# course.net
KiCad netlist of a schematic drawn in Altium Designer
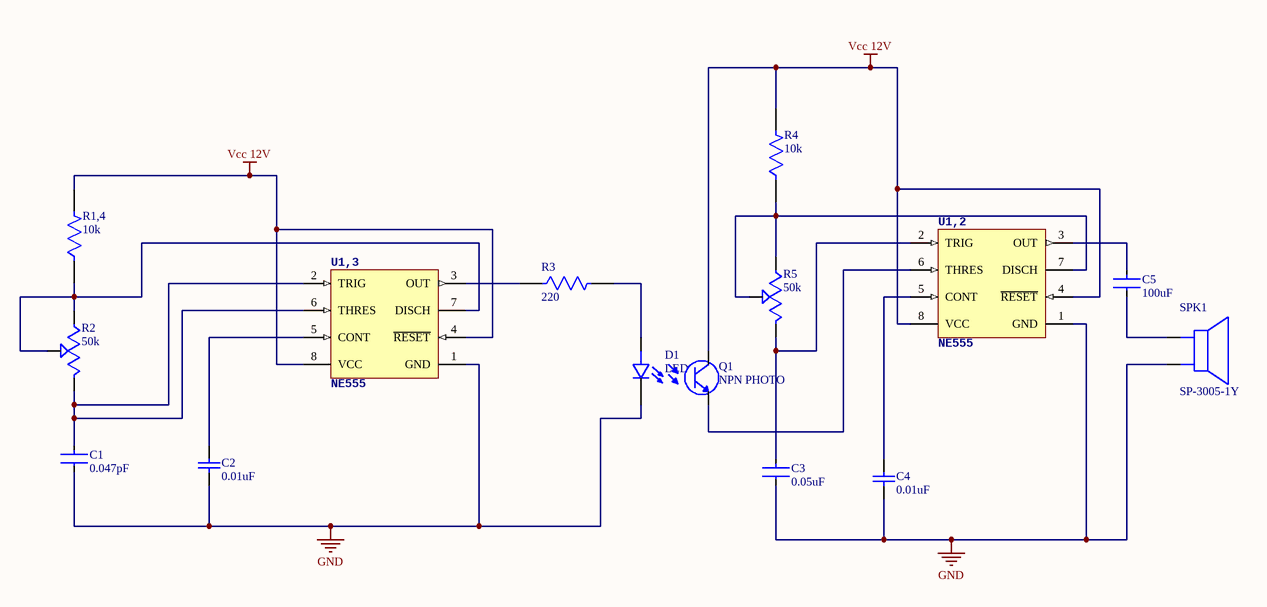
[diagram p0: course.SchDoc]

(export (version "E")
  (design (tool "Eeschema 10.0.6"))
  (components
    (comp (ref "C1")
      (value "0.047pF")
      (footprint "C0603C473M5RAC7867")
      (description "CAP CER 0.047UF 50V X7R 0603")
      (fields (field (name "TOLERANCE") "0.2") (field (name "MANUFACTURER") "KEMET"))
      (libsource (lib "course") (part "C0603C473M5RAC7867"))
    )
    (comp (ref "C2")
      (value "0.01uF")
      (footprint "CAPC1206(3216)100_L")
      (description "Cap Ceramic 0.01uF 50V X7R 10% SMD 1206 125°C Plastic T/R")
      (fields (field (name "TOLERANCE") "Â±10%"))
      (libsource (lib "course") (part "C1206C103K5RAC7025"))
    )
    (comp (ref "C3")
      (value "0.05uF")
      (footprint "FP-C0805C-DN-IPC_A")
      (description "CAP CER 0.056UF 50V 10% X7R 0805")
      (fields
        (field (name "OCTOPART") "https://octopart.com/c0805c563k5ractu-kemet-10470779")
        (field (name "TOLERANCE") "0.1")
      )
      (libsource (lib "course") (part "C0805C563K5RACTU"))
    )
    (comp (ref "C4")
      (value "0.01uF")
      (footprint "CAPC1206(3216)100_L")
      (description "Cap Ceramic 0.01uF 50V X7R 10% SMD 1206 125°C Plastic T/R")
      (fields (field (name "TOLERANCE") "Â±10%"))
      (libsource (lib "course") (part "C1206C103K5RAC7025"))
    )
    (comp (ref "C5")
      (value "100uF")
      (footprint "FP-EMK325A-M-IPC_A")
      (description "CAP CER 100UF 16V X5R 1210")
      (fields
        (field (name "OCTOPART") "https://octopart.com/emk325abj107mm-t-taiyo+yuden-20815747")
        (field (name "MANUFACTURER PART NUMBER") "EMK325ABJ107MM-T")
      )
      (libsource (lib "course") (part "EMK325ABJ107MM-T"))
    )
    (comp (ref "D1")
      (value "LED")
      (description "850 nm 100 mA Â±28Â° Surface Mount High Speed Infrared Emitting Diode")
      (fields (field (name "MP") "VSMY2853G"))
      (libsource (lib "course") (part "VSMY2853G"))
    )
    (comp (ref "Q1")
      (value "NPN PHOTO")
      (footprint "XDCR_VEMT2523X01")
      (description "PHOTOTRANSISTOR 470 TO 1090 NM")
      (fields (field (name "MP") "VEMT2523X01"))
      (libsource (lib "course") (part "VEMT2523X01"))
    )
    (comp (ref "R1,4")
      (value "10k")
      (description "10kΩ ±5% 0.125W 0805 Thick Film Chip Resistor AEC-Q200 compliant")
      (fields (field (name "TOLERANCE") "5%"))
      (libsource (lib "course") (part "RMCF0805JT10K0"))
    )
    (comp (ref "R2")
      (value "50k")
      (footprint "TRIM_PVG5A503C03R00")
      (description "50 kOhms 0.25W, 1/4W J Lead Surface Mount Trimmer Potentiometer Cermet 11 Turn Top Adjustment")
      (fields (field (name "MF") "Bourns") (field (name "MP") "PVG5A503C03R00"))
      (libsource (lib "course") (part "PVG5A503C03R00"))
    )
    (comp (ref "R3")
      (value "220")
      (footprint "FP-MCU0805-IPC_A")
      (description "Res Thin Film 0805 220 Ohm 1% 1/8W 50ppm/C Molded SMD SMD Paper T/R")
      (fields (field (name "TOLERANCE") "1%"))
      (libsource (lib "course") (part "MCU08050C2200FP500"))
    )
    (comp (ref "R4")
      (value "10k")
      (description "10kΩ ±5% 0.125W 0805 Thick Film Chip Resistor AEC-Q200 compliant")
      (fields (field (name "TOLERANCE") "5%"))
      (libsource (lib "course") (part "RMCF0805JT10K0"))
    )
    (comp (ref "R5")
      (value "50k")
      (footprint "TRIM_PVG5A503C03R00")
      (description "50 kOhms 0.25W, 1/4W J Lead Surface Mount Trimmer Potentiometer Cermet 11 Turn Top Adjustment")
      (fields (field (name "MF") "Bourns") (field (name "MP") "PVG5A503C03R00"))
      (libsource (lib "course") (part "PVG5A503C03R00"))
    )
    (comp (ref "SPK1")
      (value "SP-3005-1Y")
      (description "SPEAKER, 92DB SENSITIVITY, 30MM")
      (fields (field (name "MANUFACTURER") "Soberton"))
      (libsource (lib "course") (part "SP-3005-1Y"))
    )
    (comp (ref "U1,2")
      (value "NE555")
      (footprint "D0008A_L")
      (description "Precision Timer, 4.5 to 16 V, 0 to 70 degC, 8-Pin SOIC (D), Green (RoHS & no Sb/Br), Tube")
      (fields (field (name "MANUFACTURER") "Texas Instruments"))
      (libsource (lib "course") (part "NE555D"))
    )
    (comp (ref "U1,3")
      (value "NE555")
      (footprint "D0008A_L")
      (description "Precision Timer, 4.5 to 16 V, 0 to 70 degC, 8-Pin SOIC (D), Green (RoHS & no Sb/Br), Tube")
      (fields (field (name "MANUFACTURER") "Texas Instruments"))
      (libsource (lib "course") (part "NE555D"))
    )
  )
  (nets
    (net (code "1") (name "GND") (class "Default")
      (node (ref "C1") (pin "2") (pinfunction "2_2") (pintype "passive"))
      (node (ref "C2") (pin "1") (pinfunction "1_1") (pintype "passive"))
      (node (ref "C3") (pin "2") (pinfunction "2_2") (pintype "passive"))
      (node (ref "C4") (pin "1") (pinfunction "1_1") (pintype "passive"))
      (node (ref "D1") (pin "1") (pinfunction "1_1") (pintype "passive"))
      (node (ref "SPK1") (pin "2") (pinfunction "2_2") (pintype "passive"))
      (node (ref "U1,2") (pin "1") (pinfunction "GND_1") (pintype "power_in"))
      (node (ref "U1,3") (pin "1") (pinfunction "GND_1") (pintype "power_in"))
    )
    (net (code "2") (name "Net-(C5-Pad1)") (class "Default")
      (node (ref "C5") (pin "1") (pinfunction "1_1") (pintype "passive"))
      (node (ref "SPK1") (pin "1") (pinfunction "1_1") (pintype "passive"))
    )
    (net (code "3") (name "Net-(D1-Pad2)") (class "Default")
      (node (ref "D1") (pin "2") (pinfunction "2_2") (pintype "passive"))
      (node (ref "R3") (pin "2") (pinfunction "2_2") (pintype "passive"))
    )
    (net (code "4") (name "Net-(U1,2-CONT)") (class "Default")
      (node (ref "C4") (pin "2") (pinfunction "2_2") (pintype "passive"))
      (node (ref "U1,2") (pin "5") (pinfunction "CONT_5") (pintype "input"))
    )
    (net (code "5") (name "Net-(U1,2-DISCH)") (class "Default")
      (node (ref "R4") (pin "1") (pinfunction "1_1") (pintype "passive"))
      (node (ref "R5") (pin "1") (pinfunction "1_1") (pintype "passive"))
      (node (ref "R5") (pin "2") (pinfunction "2_2") (pintype "passive"))
      (node (ref "U1,2") (pin "7") (pinfunction "DISCH_7") (pintype "open_collector"))
    )
    (net (code "6") (name "Net-(U1,2-OUT)") (class "Default")
      (node (ref "C5") (pin "2") (pinfunction "2_2") (pintype "passive"))
      (node (ref "U1,2") (pin "3") (pinfunction "OUT_3") (pintype "output"))
    )
    (net (code "7") (name "Net-(U1,2-THRES)") (class "Default")
      (node (ref "Q1") (pin "2") (pinfunction "2_2") (pintype "passive"))
      (node (ref "U1,2") (pin "6") (pinfunction "THRES_6") (pintype "input"))
    )
    (net (code "8") (name "Net-(U1,2-TRIG)") (class "Default")
      (node (ref "C3") (pin "1") (pinfunction "1_1") (pintype "passive"))
      (node (ref "R5") (pin "3") (pinfunction "3_3") (pintype "passive"))
      (node (ref "U1,2") (pin "2") (pinfunction "TRIG_2") (pintype "input"))
    )
    (net (code "9") (name "Net-(U1,3-CONT)") (class "Default")
      (node (ref "C2") (pin "2") (pinfunction "2_2") (pintype "passive"))
      (node (ref "U1,3") (pin "5") (pinfunction "CONT_5") (pintype "input"))
    )
    (net (code "10") (name "Net-(U1,3-DISCH)") (class "Default")
      (node (ref "R1,4") (pin "1") (pinfunction "1_1") (pintype "passive"))
      (node (ref "R2") (pin "1") (pinfunction "1_1") (pintype "passive"))
      (node (ref "R2") (pin "2") (pinfunction "2_2") (pintype "passive"))
      (node (ref "U1,3") (pin "7") (pinfunction "DISCH_7") (pintype "open_collector"))
    )
    (net (code "11") (name "Net-(U1,3-OUT)") (class "Default")
      (node (ref "R3") (pin "1") (pinfunction "1_1") (pintype "passive"))
      (node (ref "U1,3") (pin "3") (pinfunction "OUT_3") (pintype "output"))
    )
    (net (code "12") (name "Net-(U1,3-THRES)") (class "Default")
      (node (ref "C1") (pin "1") (pinfunction "1_1") (pintype "passive"))
      (node (ref "R2") (pin "3") (pinfunction "3_3") (pintype "passive"))
      (node (ref "U1,3") (pin "2") (pinfunction "TRIG_2") (pintype "input"))
      (node (ref "U1,3") (pin "6") (pinfunction "THRES_6") (pintype "input"))
    )
    (net (code "13") (name "Vcc 12V") (class "Default")
      (node (ref "Q1") (pin "1") (pinfunction "1_1") (pintype "passive"))
      (node (ref "R1,4") (pin "2") (pinfunction "2_2") (pintype "passive"))
      (node (ref "R4") (pin "2") (pinfunction "2_2") (pintype "passive"))
      (node (ref "U1,2") (pin "4") (pinfunction "~{RESET}_4") (pintype "input"))
      (node (ref "U1,2") (pin "8") (pinfunction "VCC_8") (pintype "power_in"))
      (node (ref "U1,3") (pin "4") (pinfunction "~{RESET}_4") (pintype "input"))
      (node (ref "U1,3") (pin "8") (pinfunction "VCC_8") (pintype "power_in"))
    )
  )
)
